# OpenBook_v38.net
KiCad netlist of a schematic drawn in EAGLE
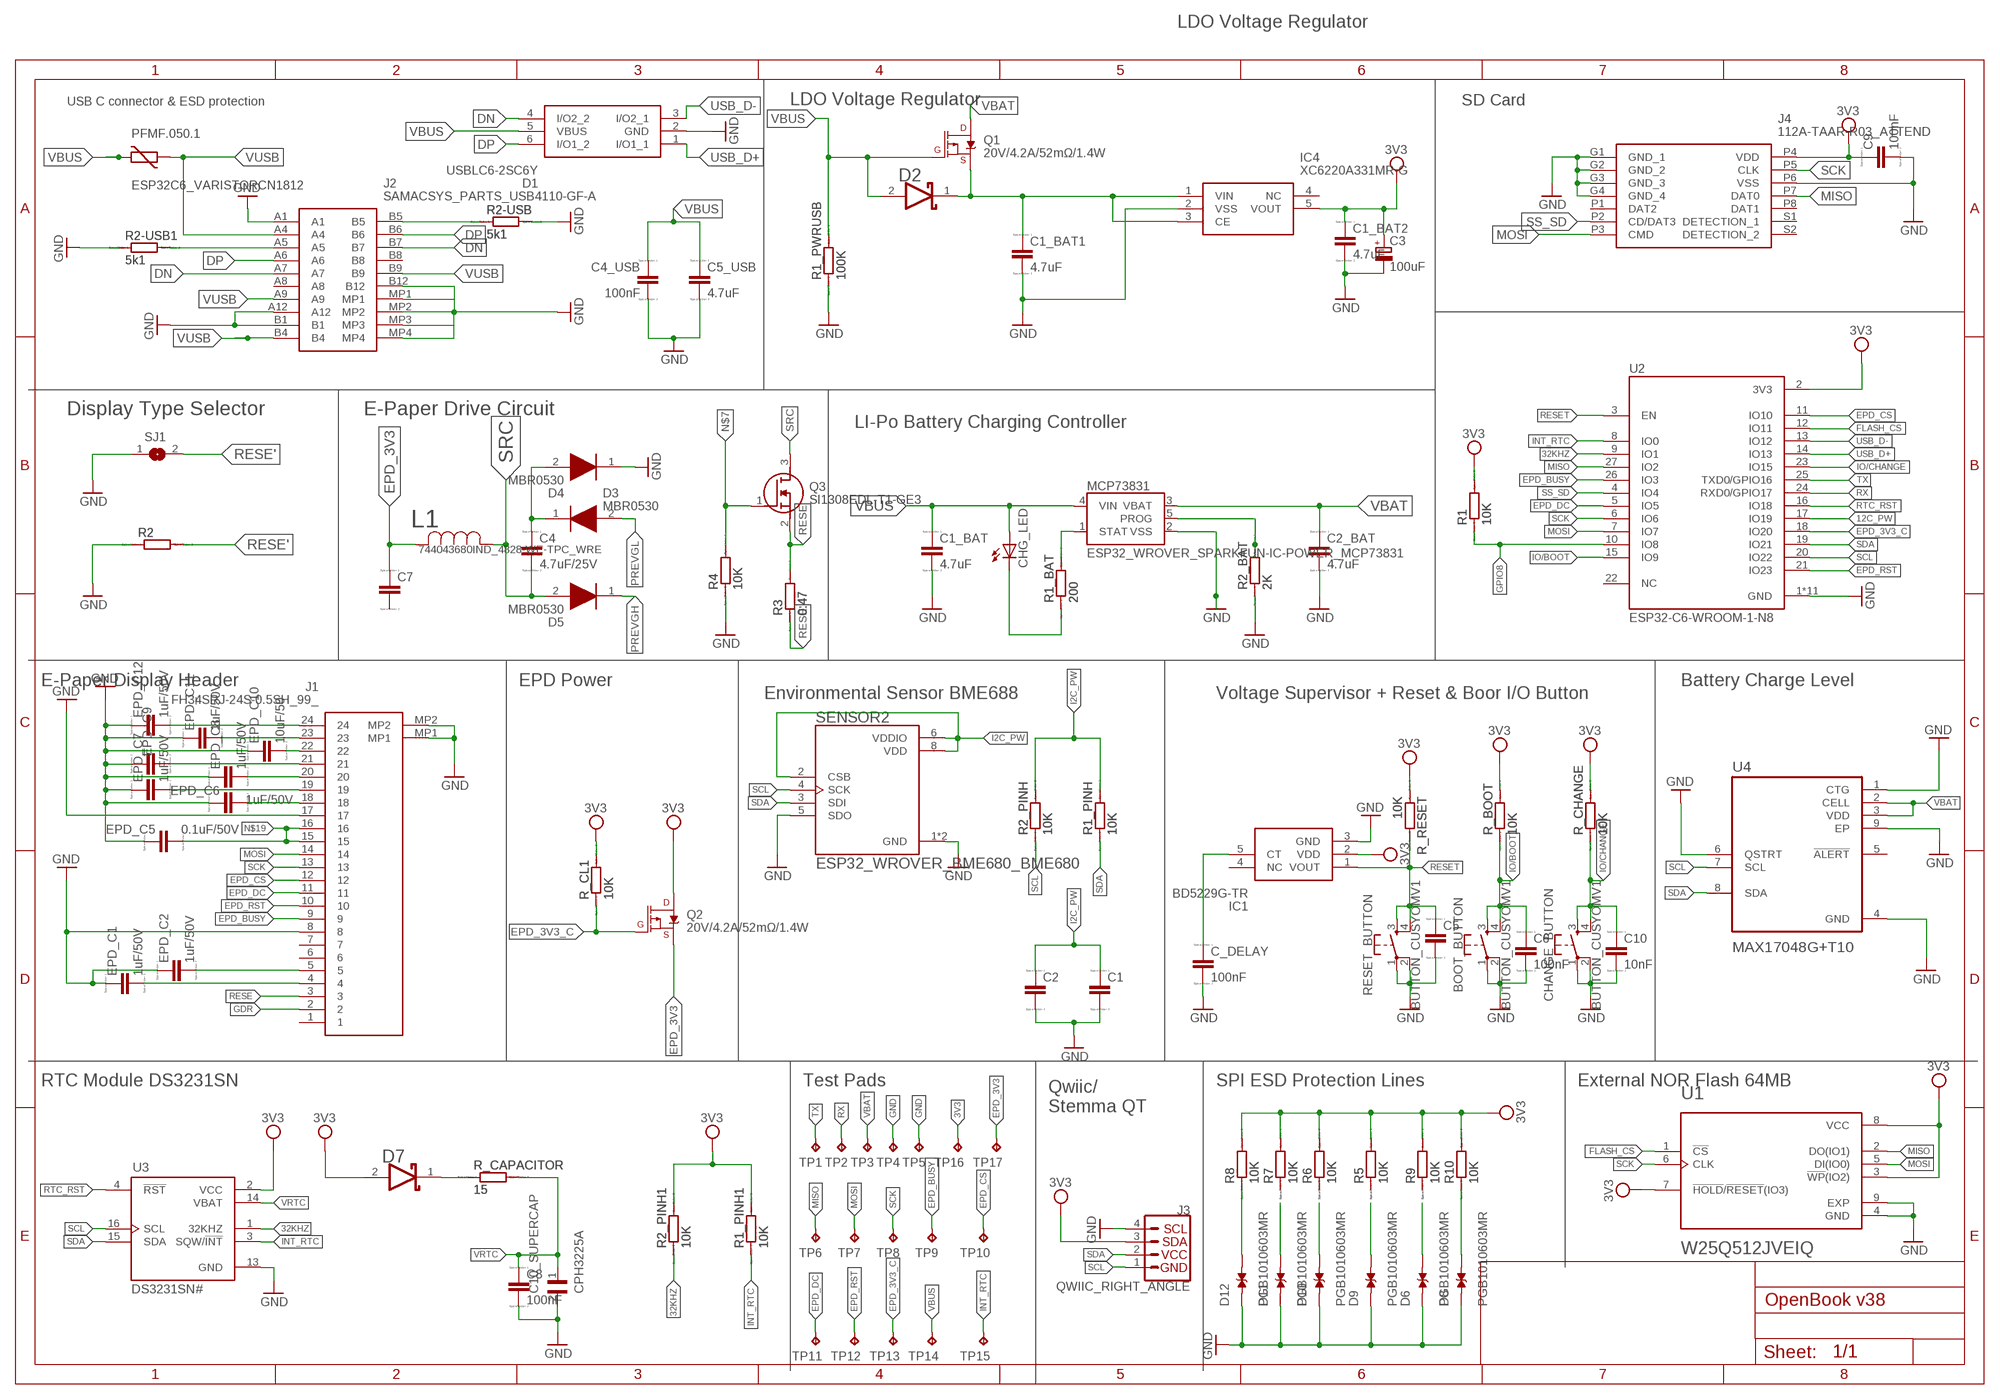
[diagram p0: schematic, sheet 1]

(export (version "E")
  (design (tool "Eeschema 10.0.6"))
  (components
    (comp (ref "BOOT_BUTTON")
      (value "BUTTON_CUSYOMV1")
      (footprint "eagle-import:MYBUTTON")
      (libsource (lib "eagle-import") (part "BUTTON_CUSYOMV1"))
    )
    (comp (ref "C1")
      (value "EAGLE-LTSPICE_CC0402")
      (footprint "eagle-import:EAGLE-LTSPICE_C0402")
      (libsource (lib "eagle-import") (part "EAGLE-LTSPICE_CC0402"))
    )
    (comp (ref "C1_BAT")
      (value "4.7uF")
      (footprint "eagle-import:EAGLE-LTSPICE_C0402")
      (libsource (lib "eagle-import") (part "EAGLE-LTSPICE_CC0402"))
    )
    (comp (ref "C1_BAT1")
      (value "4.7uF")
      (footprint "eagle-import:EAGLE-LTSPICE_C0402")
      (libsource (lib "eagle-import") (part "EAGLE-LTSPICE_CC0402"))
    )
    (comp (ref "C1_BAT2")
      (value "4.7uF")
      (footprint "eagle-import:EAGLE-LTSPICE_C0402")
      (libsource (lib "eagle-import") (part "EAGLE-LTSPICE_CC0402"))
    )
    (comp (ref "C2")
      (value "EAGLE-LTSPICE_CC0402")
      (footprint "eagle-import:EAGLE-LTSPICE_C0402")
      (libsource (lib "eagle-import") (part "EAGLE-LTSPICE_CC0402"))
    )
    (comp (ref "C2_BAT")
      (value "4.7uF")
      (footprint "eagle-import:EAGLE-LTSPICE_C0402")
      (libsource (lib "eagle-import") (part "EAGLE-LTSPICE_CC0402"))
    )
    (comp (ref "C3")
      (value "100uF")
      (footprint "eagle-import:RCL_CT3528")
      (libsource (lib "eagle-import") (part "RCL_CPOL-EUCT3528"))
    )
    (comp (ref "C4")
      (value "4.7uF/25V")
      (footprint "eagle-import:EAGLE-LTSPICE_C0402")
      (libsource (lib "eagle-import") (part "EAGLE-LTSPICE_CC0402"))
    )
    (comp (ref "C4_USB")
      (value "100nF")
      (footprint "eagle-import:EAGLE-LTSPICE_C0402")
      (libsource (lib "eagle-import") (part "EAGLE-LTSPICE_CC0402"))
    )
    (comp (ref "C5")
      (value "EAGLE-LTSPICE_CC0402")
      (footprint "eagle-import:EAGLE-LTSPICE_C0402")
      (libsource (lib "eagle-import") (part "EAGLE-LTSPICE_CC0402"))
    )
    (comp (ref "C5_USB")
      (value "4.7uF")
      (footprint "eagle-import:EAGLE-LTSPICE_C0402")
      (libsource (lib "eagle-import") (part "EAGLE-LTSPICE_CC0402"))
    )
    (comp (ref "C6")
      (value "100nF")
      (footprint "eagle-import:EAGLE-LTSPICE_C0402")
      (libsource (lib "eagle-import") (part "EAGLE-LTSPICE_CC0402"))
    )
    (comp (ref "C7")
      (value "EAGLE-LTSPICE_CC0402")
      (footprint "eagle-import:EAGLE-LTSPICE_C0402")
      (libsource (lib "eagle-import") (part "EAGLE-LTSPICE_CC0402"))
    )
    (comp (ref "C8")
      (value "100nF")
      (footprint "eagle-import:EAGLE-LTSPICE_C0402")
      (libsource (lib "eagle-import") (part "EAGLE-LTSPICE_CC0402"))
    )
    (comp (ref "C9")
      (value "100nF")
      (footprint "eagle-import:EAGLE-LTSPICE_C0402")
      (libsource (lib "eagle-import") (part "EAGLE-LTSPICE_CC0402"))
    )
    (comp (ref "C10")
      (value "10nF")
      (footprint "eagle-import:EAGLE-LTSPICE_C0402")
      (libsource (lib "eagle-import") (part "EAGLE-LTSPICE_CC0402"))
    )
    (comp (ref "C10_SUPERCAP")
      (value "CPH3225A")
      (footprint "eagle-import:CAPCP3225X100N")
      (fields (field (name "MF") "Seiko Instruments"))
      (libsource (lib "eagle-import") (part "CPH3225A"))
    )
    (comp (ref "CHANGE_BUTTON")
      (value "BUTTON_CUSYOMV1")
      (footprint "eagle-import:MYBUTTON")
      (libsource (lib "eagle-import") (part "BUTTON_CUSYOMV1"))
    )
    (comp (ref "CHG_LED")
      (value "ADAFRUIT_LEDCHIP-LED0603")
      (footprint "eagle-import:ADAFRUIT_CHIP-LED0603")
      (libsource (lib "eagle-import") (part "ADAFRUIT_LEDCHIP-LED0603"))
    )
    (comp (ref "C_DELAY")
      (value "100nF")
      (footprint "eagle-import:EAGLE-LTSPICE_C0402")
      (libsource (lib "eagle-import") (part "EAGLE-LTSPICE_CC0402"))
    )
    (comp (ref "D1")
      (value "USBLC6-2SC6Y")
      (footprint "eagle-import:SOT95P280X145-6N")
      (fields (field (name "MF") "STMicroelectronics"))
      (libsource (lib "eagle-import") (part "USBLC6-2SC6Y"))
    )
    (comp (ref "D2")
      (value "ESP32_WROVER_AVX---SD0805S020S1R0_AVX_SD0805S020S1R0_0_0AVX_SD0805S020S1R0_0_0")
      (footprint "eagle-import:ESP32_WROVER_AVX---SD0805S020S1R0_AVX_SD0805S020S1R0_0")
      (fields
        (field (name "DIGIKEY_PART_NUMBER") "478-7800-1-ND")
        (field (name "MF") "AVX")
        (field (name "MOUSER_PART_NUMBER") "581-SD0805S020S1R0")
      )
      (libsource (lib "eagle-import") (part "ESP32_WROVER_AVX---SD0805S020S1R0_AVX_SD0805S020S1R0_0_0AVX_SD0805S020S1R0_0_0"))
    )
    (comp (ref "D3")
      (value "MBR0530")
      (footprint "eagle-import:SOD3716X135N")
      (fields (field (name "MF") "ON Semiconductor"))
      (libsource (lib "eagle-import") (part "MBR0530"))
    )
    (comp (ref "D4")
      (value "MBR0530")
      (footprint "eagle-import:SOD3716X135N")
      (fields (field (name "MF") "ON Semiconductor"))
      (libsource (lib "eagle-import") (part "MBR0530"))
    )
    (comp (ref "D5")
      (value "MBR0530")
      (footprint "eagle-import:SOD3716X135N")
      (fields (field (name "MF") "ON Semiconductor"))
      (libsource (lib "eagle-import") (part "MBR0530"))
    )
    (comp (ref "D6")
      (value "PGB1010603MR")
      (footprint "eagle-import:DIOC1608X36N")
      (fields (field (name "MF") "Littelfuse Inc."))
      (libsource (lib "eagle-import") (part "PGB1010603MR"))
    )
    (comp (ref "D7")
      (value "ESP32_WROVER_AVX---SD0805S020S1R0_AVX_SD0805S020S1R0_0_0AVX_SD0805S020S1R0_0_0")
      (footprint "eagle-import:ESP32_WROVER_AVX---SD0805S020S1R0_AVX_SD0805S020S1R0_0")
      (fields
        (field (name "DIGIKEY_PART_NUMBER") "478-7800-1-ND")
        (field (name "MF") "AVX")
        (field (name "MOUSER_PART_NUMBER") "581-SD0805S020S1R0")
      )
      (libsource (lib "eagle-import") (part "ESP32_WROVER_AVX---SD0805S020S1R0_AVX_SD0805S020S1R0_0_0AVX_SD0805S020S1R0_0_0"))
    )
    (comp (ref "D8")
      (value "PGB1010603MR")
      (footprint "eagle-import:DIOC1608X36N")
      (fields (field (name "MF") "Littelfuse Inc."))
      (libsource (lib "eagle-import") (part "PGB1010603MR"))
    )
    (comp (ref "D9")
      (value "PGB1010603MR")
      (footprint "eagle-import:DIOC1608X36N")
      (fields (field (name "MF") "Littelfuse Inc."))
      (libsource (lib "eagle-import") (part "PGB1010603MR"))
    )
    (comp (ref "D10")
      (value "PGB1010603MR")
      (footprint "eagle-import:DIOC1608X36N")
      (fields (field (name "MF") "Littelfuse Inc."))
      (libsource (lib "eagle-import") (part "PGB1010603MR"))
    )
    (comp (ref "D11")
      (value "PGB1010603MR")
      (footprint "eagle-import:DIOC1608X36N")
      (fields (field (name "MF") "Littelfuse Inc."))
      (libsource (lib "eagle-import") (part "PGB1010603MR"))
    )
    (comp (ref "D12")
      (value "PGB1010603MR")
      (footprint "eagle-import:DIOC1608X36N")
      (fields (field (name "MF") "Littelfuse Inc."))
      (libsource (lib "eagle-import") (part "PGB1010603MR"))
    )
    (comp (ref "EPD_C1")
      (value "1uF/50V")
      (footprint "eagle-import:EAGLE-LTSPICE_C0402")
      (libsource (lib "eagle-import") (part "EAGLE-LTSPICE_CC0402"))
    )
    (comp (ref "EPD_C2")
      (value "1uF/50V")
      (footprint "eagle-import:EAGLE-LTSPICE_C0402")
      (libsource (lib "eagle-import") (part "EAGLE-LTSPICE_CC0402"))
    )
    (comp (ref "EPD_C5")
      (value "0.1uF/50V")
      (footprint "eagle-import:EAGLE-LTSPICE_C0402")
      (libsource (lib "eagle-import") (part "EAGLE-LTSPICE_CC0402"))
    )
    (comp (ref "EPD_C6")
      (value "1uF/50V")
      (footprint "eagle-import:EAGLE-LTSPICE_C0402")
      (libsource (lib "eagle-import") (part "EAGLE-LTSPICE_CC0402"))
    )
    (comp (ref "EPD_C7")
      (value "1uF/50V")
      (footprint "eagle-import:EAGLE-LTSPICE_C0402")
      (libsource (lib "eagle-import") (part "EAGLE-LTSPICE_CC0402"))
    )
    (comp (ref "EPD_C8")
      (value "1uF/50V")
      (footprint "eagle-import:EAGLE-LTSPICE_C0402")
      (libsource (lib "eagle-import") (part "EAGLE-LTSPICE_CC0402"))
    )
    (comp (ref "EPD_C9")
      (value "EAGLE-LTSPICE_CC0402")
      (footprint "eagle-import:EAGLE-LTSPICE_C0402")
      (libsource (lib "eagle-import") (part "EAGLE-LTSPICE_CC0402"))
    )
    (comp (ref "EPD_C10")
      (value "10uF/50")
      (footprint "eagle-import:EAGLE-LTSPICE_C0402")
      (libsource (lib "eagle-import") (part "EAGLE-LTSPICE_CC0402"))
    )
    (comp (ref "EPD_C11")
      (value "1uF/50V")
      (footprint "eagle-import:EAGLE-LTSPICE_C0402")
      (libsource (lib "eagle-import") (part "EAGLE-LTSPICE_CC0402"))
    )
    (comp (ref "EPD_C12")
      (value "1uF/50V")
      (footprint "eagle-import:EAGLE-LTSPICE_C0402")
      (libsource (lib "eagle-import") (part "EAGLE-LTSPICE_CC0402"))
    )
    (comp (ref "IC1")
      (value "BD5229G-TR")
      (footprint "eagle-import:SOT95P280X125-5N")
      (fields (field (name "MOUSER_PART_NUMBER") "755-BD5229G-TR"))
      (libsource (lib "eagle-import") (part "BD5229G-TR"))
    )
    (comp (ref "IC4")
      (value "XC6220A331MR-G")
      (footprint "eagle-import:SOT95P280X120-5N")
      (fields (field (name "MOUSER_PART_NUMBER") "865-XC6220A331MR-G"))
      (libsource (lib "eagle-import") (part "XC6220A331MR-G"))
    )
    (comp (ref "J1")
      (value "FH34SRJ-24S-0.5SH_99_")
      (footprint "eagle-import:FH34SRJ24S05SH99")
      (fields
        (field (name "MANUFACTURER_PART_NUMBER") "FH34SRJ-24S-0.5SH(99)")
        (field (name "MOUSER_PART_NUMBER") "798-FH34SRJ24S05SH99")
      )
      (libsource (lib "eagle-import") (part "FH34SRJ-24S-0.5SH_99_"))
    )
    (comp (ref "J2")
      (value "SAMACSYS_PARTS_USB4110-GF-A")
      (footprint "eagle-import:SAMACSYS_PARTS_USB4110GFA")
      (fields
        (field (name "MANUFACTURER_PART_NUMBER") "USB4110-GF-A")
        (field (name "MOUSER_PART_NUMBER") "640-USB4110-GF-A")
      )
      (libsource (lib "eagle-import") (part "SAMACSYS_PARTS_USB4110-GF-A"))
    )
    (comp (ref "J3")
      (value "QWIIC_RIGHT_ANGLE")
      (footprint "eagle-import:JST04_1MM_RA")
      (libsource (lib "eagle-import") (part "QWIIC_CONNECTORJS-1MM"))
    )
    (comp (ref "J4")
      (value "112A-TAAR-R03_ATTEND")
      (footprint "eagle-import:112ATAARR03ATTEND")
      (fields (field (name "MANUFACTURER_PART_NUMBER") "112A-TAAR-R03 ATTEND"))
      (libsource (lib "eagle-import") (part "112A-TAAR-R03_ATTEND"))
    )
    (comp (ref "L1")
      (value "744043680IND_4828-WE-TPC_WRE")
      (footprint "eagle-import:IND_4828-WE-TPC_WRE")
      (fields
        (field (name "MANUFACTURER_PART_NUMBER") "744043680")
        (field (name "COPYRIGHT") "Copyright (C) 2024 Ultra Librarian. All rights reserved.")
      )
      (libsource (lib "eagle-import") (part "744043680IND_4828-WE-TPC_WRE"))
    )
    (comp (ref "MCP73831")
      (value "ESP32_WROVER_SPARKFUN-IC-POWER_MCP73831")
      (footprint "eagle-import:ESP32_WROVER_SPARKFUN-IC-POWER_SOT23-5")
      (libsource (lib "eagle-import") (part "ESP32_WROVER_SPARKFUN-IC-POWER_MCP73831"))
    )
    (comp (ref "PFMF.050.1")
      (value "ESP32C6_VARISTORCN1812")
      (footprint "eagle-import:ESP32C6_VARISTOR_CT_CN1812")
      (libsource (lib "eagle-import") (part "ESP32C6_VARISTORCN1812"))
    )
    (comp (ref "Q1")
      (value "20V/4.2A/52mΩ/1.4W")
      (footprint "eagle-import:ESP32_WROVER_SPARKFUN-DISCRETESEMI_SOT23-3")
      (libsource (lib "eagle-import") (part "ESP32_WROVER_SPARKFUN-DISCRETESEMI_MOSFET_PCH-DMG2305UX-7"))
    )
    (comp (ref "Q2")
      (value "20V/4.2A/52mΩ/1.4W")
      (footprint "eagle-import:ESP32_WROVER_SPARKFUN-DISCRETESEMI_SOT23-3")
      (libsource (lib "eagle-import") (part "ESP32_WROVER_SPARKFUN-DISCRETESEMI_MOSFET_PCH-DMG2305UX-7"))
    )
    (comp (ref "Q3")
      (value "SI1308EDL-T1-GE3")
      (footprint "eagle-import:SOT65P210X110-3N")
      (fields (field (name "MF") "Vishay Siliconix"))
      (libsource (lib "eagle-import") (part "SI1308EDL-T1-GE3"))
    )
    (comp (ref "R1")
      (value "10K")
      (footprint "eagle-import:ESP32_WROVER_EAGLE-LTSPICE_R0402")
      (libsource (lib "eagle-import") (part "ESP32_WROVER_EAGLE-LTSPICE_RR0402"))
    )
    (comp (ref "R1_BAT")
      (value "200")
      (footprint "eagle-import:ESP32_WROVER_EAGLE-LTSPICE_R0402")
      (libsource (lib "eagle-import") (part "ESP32_WROVER_EAGLE-LTSPICE_RR0402"))
    )
    (comp (ref "R1_PINH")
      (value "10K")
      (footprint "eagle-import:ESP32_WROVER_EAGLE-LTSPICE_R0402")
      (libsource (lib "eagle-import") (part "ESP32_WROVER_EAGLE-LTSPICE_RR0402"))
    )
    (comp (ref "R1_PINH1")
      (value "10K")
      (footprint "eagle-import:ESP32_WROVER_EAGLE-LTSPICE_R0402")
      (libsource (lib "eagle-import") (part "ESP32_WROVER_EAGLE-LTSPICE_RR0402"))
    )
    (comp (ref "R1_PWRUSB")
      (value "100K")
      (footprint "eagle-import:ESP32_WROVER_EAGLE-LTSPICE_R0402")
      (libsource (lib "eagle-import") (part "ESP32_WROVER_EAGLE-LTSPICE_RR0402"))
    )
    (comp (ref "R2")
      (value "ESP32_WROVER_EAGLE-LTSPICE_RR0402")
      (footprint "eagle-import:ESP32_WROVER_EAGLE-LTSPICE_R0402")
      (libsource (lib "eagle-import") (part "ESP32_WROVER_EAGLE-LTSPICE_RR0402"))
    )
    (comp (ref "R2-USB")
      (value "5k1")
      (footprint "eagle-import:ESP32_WROVER_EAGLE-LTSPICE_R0402")
      (libsource (lib "eagle-import") (part "ESP32_WROVER_EAGLE-LTSPICE_RR0402"))
    )
    (comp (ref "R2-USB1")
      (value "5k1")
      (footprint "eagle-import:ESP32_WROVER_EAGLE-LTSPICE_R0402")
      (libsource (lib "eagle-import") (part "ESP32_WROVER_EAGLE-LTSPICE_RR0402"))
    )
    (comp (ref "R2_BAT")
      (value "2K")
      (footprint "eagle-import:ESP32_WROVER_EAGLE-LTSPICE_R0402")
      (libsource (lib "eagle-import") (part "ESP32_WROVER_EAGLE-LTSPICE_RR0402"))
    )
    (comp (ref "R2_PINH")
      (value "10K")
      (footprint "eagle-import:ESP32_WROVER_EAGLE-LTSPICE_R0402")
      (libsource (lib "eagle-import") (part "ESP32_WROVER_EAGLE-LTSPICE_RR0402"))
    )
    (comp (ref "R2_PINH1")
      (value "10K")
      (footprint "eagle-import:ESP32_WROVER_EAGLE-LTSPICE_R0402")
      (libsource (lib "eagle-import") (part "ESP32_WROVER_EAGLE-LTSPICE_RR0402"))
    )
    (comp (ref "R3")
      (value "0.47")
      (footprint "eagle-import:ESP32_WROVER_EAGLE-LTSPICE_R0402")
      (libsource (lib "eagle-import") (part "ESP32_WROVER_EAGLE-LTSPICE_RR0402"))
    )
    (comp (ref "R4")
      (value "10K")
      (footprint "eagle-import:ESP32_WROVER_EAGLE-LTSPICE_R0402")
      (libsource (lib "eagle-import") (part "ESP32_WROVER_EAGLE-LTSPICE_RR0402"))
    )
    (comp (ref "R5")
      (value "10K")
      (footprint "eagle-import:ESP32_WROVER_EAGLE-LTSPICE_R0402")
      (libsource (lib "eagle-import") (part "ESP32_WROVER_EAGLE-LTSPICE_RR0402"))
    )
    (comp (ref "R6")
      (value "10K")
      (footprint "eagle-import:ESP32_WROVER_EAGLE-LTSPICE_R0402")
      (libsource (lib "eagle-import") (part "ESP32_WROVER_EAGLE-LTSPICE_RR0402"))
    )
    (comp (ref "R7")
      (value "10K")
      (footprint "eagle-import:ESP32_WROVER_EAGLE-LTSPICE_R0402")
      (libsource (lib "eagle-import") (part "ESP32_WROVER_EAGLE-LTSPICE_RR0402"))
    )
    (comp (ref "R8")
      (value "10K")
      (footprint "eagle-import:ESP32_WROVER_EAGLE-LTSPICE_R0402")
      (libsource (lib "eagle-import") (part "ESP32_WROVER_EAGLE-LTSPICE_RR0402"))
    )
    (comp (ref "R9")
      (value "10K")
      (footprint "eagle-import:ESP32_WROVER_EAGLE-LTSPICE_R0402")
      (libsource (lib "eagle-import") (part "ESP32_WROVER_EAGLE-LTSPICE_RR0402"))
    )
    (comp (ref "R10")
      (value "10K")
      (footprint "eagle-import:ESP32_WROVER_EAGLE-LTSPICE_R0402")
      (libsource (lib "eagle-import") (part "ESP32_WROVER_EAGLE-LTSPICE_RR0402"))
    )
    (comp (ref "RESET_BUTTON")
      (value "BUTTON_CUSYOMV1")
      (footprint "eagle-import:MYBUTTON")
      (libsource (lib "eagle-import") (part "BUTTON_CUSYOMV1"))
    )
    (comp (ref "R_BOOT")
      (value "10K")
      (footprint "eagle-import:ESP32_WROVER_EAGLE-LTSPICE_R0402")
      (libsource (lib "eagle-import") (part "ESP32_WROVER_EAGLE-LTSPICE_RR0402"))
    )
    (comp (ref "R_CAPACITOR")
      (value "15")
      (footprint "eagle-import:ESP32_WROVER_EAGLE-LTSPICE_R0402")
      (libsource (lib "eagle-import") (part "ESP32_WROVER_EAGLE-LTSPICE_RR0402"))
    )
    (comp (ref "R_CHANGE")
      (value "10K")
      (footprint "eagle-import:ESP32_WROVER_EAGLE-LTSPICE_R0402")
      (libsource (lib "eagle-import") (part "ESP32_WROVER_EAGLE-LTSPICE_RR0402"))
    )
    (comp (ref "R_CL1")
      (value "10K")
      (footprint "eagle-import:ESP32_WROVER_EAGLE-LTSPICE_R0402")
      (libsource (lib "eagle-import") (part "ESP32_WROVER_EAGLE-LTSPICE_RR0402"))
    )
    (comp (ref "R_RESET")
      (value "10K")
      (footprint "eagle-import:ESP32_WROVER_EAGLE-LTSPICE_R0402")
      (libsource (lib "eagle-import") (part "ESP32_WROVER_EAGLE-LTSPICE_RR0402"))
    )
    (comp (ref "SENSOR2")
      (value "ESP32_WROVER_BME680_BME680")
      (footprint "eagle-import:ESP32_WROVER_BME680_PSON80P300X300X100-8N")
      (fields (field (name "MF") "Bosch Sensortec") (field (name "MP") "BME680"))
      (libsource (lib "eagle-import") (part "ESP32_WROVER_BME680_BME680"))
    )
    (comp (ref "SJ1") (value "SJ") (footprint "eagle-import:SJ") (libsource (lib "eagle-import") (part "SJ")))
    (comp (ref "TP1")
      (value "TPTP20R")
      (footprint "eagle-import:TP20R")
      (libsource (lib "eagle-import") (part "TPTP20R"))
    )
    (comp (ref "TP2")
      (value "TPTP20R")
      (footprint "eagle-import:TP20R")
      (libsource (lib "eagle-import") (part "TPTP20R"))
    )
    (comp (ref "TP3")
      (value "TPTP20R")
      (footprint "eagle-import:TP20R")
      (libsource (lib "eagle-import") (part "TPTP20R"))
    )
    (comp (ref "TP4")
      (value "TPTP20R")
      (footprint "eagle-import:TP20R")
      (libsource (lib "eagle-import") (part "TPTP20R"))
    )
    (comp (ref "TP5")
      (value "TPTP20R")
      (footprint "eagle-import:TP20R")
      (libsource (lib "eagle-import") (part "TPTP20R"))
    )
    (comp (ref "TP6")
      (value "TPTP20R")
      (footprint "eagle-import:TP20R")
      (libsource (lib "eagle-import") (part "TPTP20R"))
    )
    (comp (ref "TP7")
      (value "TPTP20R")
      (footprint "eagle-import:TP20R")
      (libsource (lib "eagle-import") (part "TPTP20R"))
    )
    (comp (ref "TP8")
      (value "TPTP20R")
      (footprint "eagle-import:TP20R")
      (libsource (lib "eagle-import") (part "TPTP20R"))
    )
    (comp (ref "TP9")
      (value "TPTP20R")
      (footprint "eagle-import:TP20R")
      (libsource (lib "eagle-import") (part "TPTP20R"))
    )
    (comp (ref "TP10")
      (value "TPTP20R")
      (footprint "eagle-import:TP20R")
      (libsource (lib "eagle-import") (part "TPTP20R"))
    )
    (comp (ref "TP11")
      (value "TPTP20R")
      (footprint "eagle-import:TP20R")
      (libsource (lib "eagle-import") (part "TPTP20R"))
    )
    (comp (ref "TP12")
      (value "TPTP20R")
      (footprint "eagle-import:TP20R")
      (libsource (lib "eagle-import") (part "TPTP20R"))
    )
    (comp (ref "TP13")
      (value "TPTP20R")
      (footprint "eagle-import:TP20R")
      (libsource (lib "eagle-import") (part "TPTP20R"))
    )
    (comp (ref "TP14")
      (value "TPTP20R")
      (footprint "eagle-import:TP20R")
      (libsource (lib "eagle-import") (part "TPTP20R"))
    )
    (comp (ref "TP15")
      (value "TPTP20R")
      (footprint "eagle-import:TP20R")
      (libsource (lib "eagle-import") (part "TPTP20R"))
    )
    (comp (ref "TP16")
      (value "TPTP20R")
      (footprint "eagle-import:TP20R")
      (libsource (lib "eagle-import") (part "TPTP20R"))
    )
    (comp (ref "TP17")
      (value "TPTP20R")
      (footprint "eagle-import:TP20R")
      (libsource (lib "eagle-import") (part "TPTP20R"))
    )
    (comp (ref "U1")
      (value "W25Q512JVEIQ")
      (footprint "eagle-import:SON127P600X800X80-9N")
      (fields (field (name "MF") "Winbond Electronics"))
      (libsource (lib "eagle-import") (part "W25Q512JVEIQ"))
    )
    (comp (ref "U2")
      (value "ESP32-C6-WROOM-1-N8")
      (footprint "eagle-import:XCVR_ESP32-C6-WROOM-1-N8")
      (fields (field (name "MF") "Espressif Systems"))
      (libsource (lib "eagle-import") (part "ESP32-C6-WROOM-1-N8"))
    )
    (comp (ref "U3")
      (value "DS3231SN#")
      (footprint "eagle-import:SOIC127P1032X265-16N")
      (fields (field (name "MF") "Analog Devices"))
      (libsource (lib "eagle-import") (part "DS3231SN#"))
    )
    (comp (ref "U4")
      (value "MAX17048G+T10")
      (footprint "eagle-import:SON50P200X200X80-9N")
      (fields (field (name "MF") "Analog Devices"))
      (libsource (lib "eagle-import") (part "MAX17048G+T10"))
    )
  )
  (nets
    (net (code "1") (name "3V3") (class "Default")
      (node (ref "C1_BAT2") (pin "1") (pinfunction "1_1") (pintype "passive"))
      (node (ref "C3") (pin "+") (pinfunction "+_+") (pintype "passive"))
      (node (ref "C9") (pin "1") (pinfunction "1_1") (pintype "passive"))
      (node (ref "D7") (pin "2") (pinfunction "ANODE_2") (pintype "bidirectional"))
      (node (ref "IC1") (pin "2") (pinfunction "VDD_2") (pintype "bidirectional"))
      (node (ref "IC4") (pin "5") (pinfunction "VOUT_5") (pintype "bidirectional"))
      (node (ref "J3") (pin "3") (pinfunction "3_3") (pintype "passive"))
      (node (ref "J4") (pin "P4") (pinfunction "VDD_P4") (pintype "bidirectional"))
      (node (ref "Q2") (pin "3") (pinfunction "D_3") (pintype "bidirectional"))
      (node (ref "R1") (pin "2") (pinfunction "2_2") (pintype "passive"))
      (node (ref "R10") (pin "2") (pinfunction "2_2") (pintype "passive"))
      (node (ref "R1_PINH1") (pin "2") (pinfunction "2_2") (pintype "passive"))
      (node (ref "R2_PINH1") (pin "2") (pinfunction "2_2") (pintype "passive"))
      (node (ref "R5") (pin "2") (pinfunction "2_2") (pintype "passive"))
      (node (ref "R6") (pin "2") (pinfunction "2_2") (pintype "passive"))
      (node (ref "R7") (pin "2") (pinfunction "2_2") (pintype "passive"))
      (node (ref "R8") (pin "2") (pinfunction "2_2") (pintype "passive"))
      (node (ref "R9") (pin "2") (pinfunction "2_2") (pintype "passive"))
      (node (ref "R_BOOT") (pin "2") (pinfunction "2_2") (pintype "passive"))
      (node (ref "R_CHANGE") (pin "2") (pinfunction "2_2") (pintype "passive"))
      (node (ref "R_CL1") (pin "2") (pinfunction "2_2") (pintype "passive"))
      (node (ref "R_RESET") (pin "1") (pinfunction "1_1") (pintype "passive"))
      (node (ref "TP16") (pin "TP") (pinfunction "TP_TP") (pintype "input"))
      (node (ref "U1") (pin "3") (pinfunction "~{WP}(IO2)_3") (pintype "bidirectional"))
      (node (ref "U1") (pin "7") (pinfunction "~{HOLD}/~{RESET}(IO3)_7") (pintype "bidirectional"))
      (node (ref "U1") (pin "8") (pinfunction "VCC_8") (pintype "power_in"))
      (node (ref "U2") (pin "2") (pinfunction "3V3_2") (pintype "power_in"))
      (node (ref "U3") (pin "2") (pinfunction "VCC_2") (pintype "power_in"))
    )
    (net (code "2") (name "12C_PW") (class "Default")
      (node (ref "U2") (pin "17") (pinfunction "IO19_17") (pintype "bidirectional"))
    )
    (net (code "3") (name "32KHZ") (class "Default")
      (node (ref "R2_PINH1") (pin "1") (pinfunction "1_1") (pintype "passive"))
      (node (ref "U2") (pin "9") (pinfunction "IO1_9") (pintype "bidirectional"))
      (node (ref "U3") (pin "1") (pinfunction "32KHZ_1") (pintype "output"))
    )
    (net (code "4") (name "DN") (class "Default")
      (node (ref "D1") (pin "4") (pinfunction "I/O2_2_4") (pintype "bidirectional"))
      (node (ref "J2") (pin "A7") (pinfunction "A7_A7") (pintype "bidirectional"))
      (node (ref "J2") (pin "B7") (pinfunction "B7_B7") (pintype "bidirectional"))
    )
    (net (code "5") (name "DP") (class "Default")
      (node (ref "D1") (pin "6") (pinfunction "I/O1_2_6") (pintype "bidirectional"))
      (node (ref "J2") (pin "A6") (pinfunction "A6_A6") (pintype "bidirectional"))
      (node (ref "J2") (pin "B6") (pinfunction "B6_B6") (pintype "bidirectional"))
    )
    (net (code "6") (name "EPD_3V3") (class "Default")
      (node (ref "C7") (pin "1") (pinfunction "1_1") (pintype "passive"))
      (node (ref "L1") (pin "2") (pinfunction "2_2") (pintype "passive"))
      (node (ref "Q2") (pin "2") (pinfunction "S_2") (pintype "bidirectional"))
      (node (ref "TP17") (pin "TP") (pinfunction "TP_TP") (pintype "input"))
    )
    (net (code "7") (name "EPD_3V3_C") (class "Default")
      (node (ref "Q2") (pin "1") (pinfunction "G_1") (pintype "bidirectional"))
      (node (ref "R_CL1") (pin "1") (pinfunction "1_1") (pintype "passive"))
      (node (ref "TP13") (pin "TP") (pinfunction "TP_TP") (pintype "input"))
      (node (ref "U2") (pin "18") (pinfunction "IO20_18") (pintype "bidirectional"))
    )
    (net (code "8") (name "EPD_BUSY") (class "Default")
      (node (ref "J1") (pin "9") (pinfunction "9_9") (pintype "bidirectional"))
      (node (ref "TP9") (pin "TP") (pinfunction "TP_TP") (pintype "input"))
      (node (ref "U2") (pin "26") (pinfunction "IO3_26") (pintype "bidirectional"))
    )
    (net (code "9") (name "EPD_CS") (class "Default")
      (node (ref "J1") (pin "12") (pinfunction "12_12") (pintype "bidirectional"))
      (node (ref "TP10") (pin "TP") (pinfunction "TP_TP") (pintype "input"))
      (node (ref "U2") (pin "11") (pinfunction "IO10_11") (pintype "bidirectional"))
    )
    (net (code "10") (name "EPD_DC") (class "Default")
      (node (ref "J1") (pin "11") (pinfunction "11_11") (pintype "bidirectional"))
      (node (ref "TP11") (pin "TP") (pinfunction "TP_TP") (pintype "input"))
      (node (ref "U2") (pin "5") (pinfunction "IO5_5") (pintype "bidirectional"))
    )
    (net (code "11") (name "EPD_RST") (class "Default")
      (node (ref "J1") (pin "10") (pinfunction "10_10") (pintype "bidirectional"))
      (node (ref "TP12") (pin "TP") (pinfunction "TP_TP") (pintype "input"))
      (node (ref "U2") (pin "21") (pinfunction "IO23_21") (pintype "bidirectional"))
    )
    (net (code "12") (name "FLASH_CS") (class "Default")
      (node (ref "U1") (pin "1") (pinfunction "~{CS}_1") (pintype "input"))
      (node (ref "U2") (pin "12") (pinfunction "IO11_12") (pintype "bidirectional"))
    )
    (net (code "13") (name "GDR") (class "Default")
      (node (ref "J1") (pin "2") (pinfunction "2_2") (pintype "bidirectional"))
    )
    (net (code "14") (name "GND") (class "Default")
      (node (ref "BOOT_BUTTON") (pin "1") (pinfunction "1_1") (pintype "passive"))
      (node (ref "BOOT_BUTTON") (pin "2") (pinfunction "2_2") (pintype "passive"))
      (node (ref "C1") (pin "2") (pinfunction "2_2") (pintype "passive"))
      (node (ref "C10") (pin "2") (pinfunction "2_2") (pintype "passive"))
      (node (ref "C10_SUPERCAP") (pin "2") (pinfunction "2_2") (pintype "passive"))
      (node (ref "C1_BAT") (pin "2") (pinfunction "2_2") (pintype "passive"))
      (node (ref "C1_BAT1") (pin "2") (pinfunction "2_2") (pintype "passive"))
      (node (ref "C1_BAT2") (pin "2") (pinfunction "2_2") (pintype "passive"))
      (node (ref "C2") (pin "2") (pinfunction "2_2") (pintype "passive"))
      (node (ref "C2_BAT") (pin "2") (pinfunction "2_2") (pintype "passive"))
      (node (ref "C3") (pin "-") (pinfunction "-_-") (pintype "passive"))
      (node (ref "C4_USB") (pin "2") (pinfunction "2_2") (pintype "passive"))
      (node (ref "C5") (pin "2") (pinfunction "2_2") (pintype "passive"))
      (node (ref "C5_USB") (pin "2") (pinfunction "2_2") (pintype "passive"))
      (node (ref "C6") (pin "2") (pinfunction "2_2") (pintype "passive"))
      (node (ref "C8") (pin "2") (pinfunction "2_2") (pintype "passive"))
      (node (ref "C9") (pin "2") (pinfunction "2_2") (pintype "passive"))
      (node (ref "CHANGE_BUTTON") (pin "1") (pinfunction "1_1") (pintype "passive"))
      (node (ref "CHANGE_BUTTON") (pin "2") (pinfunction "2_2") (pintype "passive"))
      (node (ref "C_DELAY") (pin "2") (pinfunction "2_2") (pintype "passive"))
      (node (ref "D1") (pin "2") (pinfunction "GND_2") (pintype "bidirectional"))
      (node (ref "D10") (pin "1") (pinfunction "1_1") (pintype "passive"))
      (node (ref "D11") (pin "1") (pinfunction "1_1") (pintype "passive"))
      (node (ref "D12") (pin "1") (pinfunction "1_1") (pintype "passive"))
      (node (ref "D4") (pin "1") (pinfunction "K_1") (pintype "bidirectional"))
      (node (ref "D6") (pin "1") (pinfunction "1_1") (pintype "passive"))
      (node (ref "D8") (pin "1") (pinfunction "1_1") (pintype "passive"))
      (node (ref "D9") (pin "1") (pinfunction "1_1") (pintype "passive"))
      (node (ref "EPD_C1") (pin "1") (pinfunction "1_1") (pintype "passive"))
      (node (ref "EPD_C10") (pin "1") (pinfunction "1_1") (pintype "passive"))
      (node (ref "EPD_C11") (pin "1") (pinfunction "1_1") (pintype "passive"))
      (node (ref "EPD_C12") (pin "1") (pinfunction "1_1") (pintype "passive"))
      (node (ref "EPD_C2") (pin "1") (pinfunction "1_1") (pintype "passive"))
      (node (ref "EPD_C5") (pin "1") (pinfunction "1_1") (pintype "passive"))
      (node (ref "EPD_C6") (pin "1") (pinfunction "1_1") (pintype "passive"))
      (node (ref "EPD_C7") (pin "1") (pinfunction "1_1") (pintype "passive"))
      (node (ref "EPD_C8") (pin "1") (pinfunction "1_1") (pintype "passive"))
      (node (ref "EPD_C9") (pin "1") (pinfunction "1_1") (pintype "passive"))
      (node (ref "IC1") (pin "3") (pinfunction "GND_3") (pintype "bidirectional"))
      (node (ref "IC4") (pin "2") (pinfunction "VSS_2") (pintype "bidirectional"))
      (node (ref "J1") (pin "17") (pinfunction "17_17") (pintype "bidirectional"))
      (node (ref "J1") (pin "8") (pinfunction "8_8") (pintype "bidirectional"))
      (node (ref "J1") (pin "MP1") (pinfunction "MP1_MP1") (pintype "bidirectional"))
      (node (ref "J1") (pin "MP2") (pinfunction "MP2_MP2") (pintype "bidirectional"))
      (node (ref "J2") (pin "A1") (pinfunction "A1_A1") (pintype "bidirectional"))
      (node (ref "J2") (pin "A12") (pinfunction "A12_A12") (pintype "bidirectional"))
      (node (ref "J2") (pin "B1") (pinfunction "B1_B1") (pintype "bidirectional"))
      (node (ref "J2") (pin "B12") (pinfunction "B12_B12") (pintype "bidirectional"))
      (node (ref "J2") (pin "MP1") (pinfunction "MP1_MP1") (pintype "bidirectional"))
      (node (ref "J2") (pin "MP2") (pinfunction "MP2_MP2") (pintype "bidirectional"))
      (node (ref "J2") (pin "MP3") (pinfunction "MP3_MP3") (pintype "bidirectional"))
      (node (ref "J2") (pin "MP4") (pinfunction "MP4_MP4") (pintype "bidirectional"))
      (node (ref "J3") (pin "4") (pinfunction "4_4") (pintype "passive"))
      (node (ref "J4") (pin "G1") (pinfunction "GND_1_G1") (pintype "bidirectional"))
      (node (ref "J4") (pin "G2") (pinfunction "GND_2_G2") (pintype "bidirectional"))
      (node (ref "J4") (pin "G3") (pinfunction "GND_3_G3") (pintype "bidirectional"))
      (node (ref "J4") (pin "G4") (pinfunction "GND_4_G4") (pintype "bidirectional"))
      (node (ref "J4") (pin "P6") (pinfunction "VSS_P6") (pintype "bidirectional"))
      (node (ref "MCP73831") (pin "2") (pinfunction "VSS_2") (pintype "power_in"))
      (node (ref "R1_PWRUSB") (pin "1") (pinfunction "1_1") (pintype "passive"))
      (node (ref "R2") (pin "1") (pinfunction "1_1") (pintype "passive"))
      (node (ref "R2-USB") (pin "2") (pinfunction "2_2") (pintype "passive"))
      (node (ref "R2-USB1") (pin "1") (pinfunction "1_1") (pintype "passive"))
      (node (ref "R2_BAT") (pin "1") (pinfunction "1_1") (pintype "passive"))
      (node (ref "R4") (pin "1") (pinfunction "1_1") (pintype "passive"))
      (node (ref "RESET_BUTTON") (pin "1") (pinfunction "1_1") (pintype "passive"))
      (node (ref "RESET_BUTTON") (pin "2") (pinfunction "2_2") (pintype "passive"))
      (node (ref "SENSOR2") (pin "1") (pinfunction "GND_1") (pintype "power_in"))
      (node (ref "SENSOR2") (pin "5") (pinfunction "SDO_5") (pintype "bidirectional"))
      (node (ref "SENSOR2") (pin "7") (pinfunction "GND_7") (pintype "power_in"))
      (node (ref "SJ1") (pin "1") (pinfunction "1_1") (pintype "passive"))
      (node (ref "TP4") (pin "TP") (pinfunction "TP_TP") (pintype "input"))
      (node (ref "TP5") (pin "TP") (pinfunction "TP_TP") (pintype "input"))
      (node (ref "U1") (pin "4") (pinfunction "GND_4") (pintype "power_in"))
      (node (ref "U1") (pin "9") (pinfunction "EXP_9") (pintype "passive"))
      (node (ref "U2") (pin "1") (pinfunction "GND_1") (pintype "power_in"))
      (node (ref "U2") (pin "28") (pinfunction "GND_28") (pintype "power_in"))
      (node (ref "U2") (pin "29_1") (pinfunction "GND_29_1") (pintype "power_in"))
      (node (ref "U2") (pin "29_2") (pinfunction "GND_29_2") (pintype "power_in"))
      (node (ref "U2") (pin "29_3") (pinfunction "GND_29_3") (pintype "power_in"))
      (node (ref "U2") (pin "29_4") (pinfunction "GND_29_4") (pintype "power_in"))
      (node (ref "U2") (pin "29_5") (pinfunction "GND_29_5") (pintype "power_in"))
      (node (ref "U2") (pin "29_6") (pinfunction "GND_29_6") (pintype "power_in"))
      (node (ref "U2") (pin "29_7") (pinfunction "GND_29_7") (pintype "power_in"))
      (node (ref "U2") (pin "29_8") (pinfunction "GND_29_8") (pintype "power_in"))
      (node (ref "U2") (pin "29_9") (pinfunction "GND_29_9") (pintype "power_in"))
      (node (ref "U3") (pin "13") (pinfunction "GND_13") (pintype "power_in"))
      (node (ref "U4") (pin "1") (pinfunction "CTG_1") (pintype "power_in"))
      (node (ref "U4") (pin "4") (pinfunction "GND_4") (pintype "power_in"))
      (node (ref "U4") (pin "6") (pinfunction "QSTRT_6") (pintype "input"))
      (node (ref "U4") (pin "9") (pinfunction "EP_9") (pintype "power_in"))
    )
    (net (code "15") (name "GPIO8") (class "Default")
      (node (ref "R1") (pin "1") (pinfunction "1_1") (pintype "passive"))
      (node (ref "U2") (pin "10") (pinfunction "IO8_10") (pintype "bidirectional"))
    )
    (net (code "16") (name "I2C_PW") (class "Default")
      (node (ref "C1") (pin "1") (pinfunction "1_1") (pintype "passive"))
      (node (ref "C2") (pin "1") (pinfunction "1_1") (pintype "passive"))
      (node (ref "R1_PINH") (pin "2") (pinfunction "2_2") (pintype "passive"))
      (node (ref "R2_PINH") (pin "2") (pinfunction "2_2") (pintype "passive"))
      (node (ref "SENSOR2") (pin "2") (pinfunction "CSB_2") (pintype "input"))
      (node (ref "SENSOR2") (pin "6") (pinfunction "VDDIO_6") (pintype "power_in"))
      (node (ref "SENSOR2") (pin "8") (pinfunction "VDD_8") (pintype "power_in"))
    )
    (net (code "17") (name "INT_RTC") (class "Default")
      (node (ref "R1_PINH1") (pin "1") (pinfunction "1_1") (pintype "passive"))
      (node (ref "TP15") (pin "TP") (pinfunction "TP_TP") (pintype "input"))
      (node (ref "U2") (pin "8") (pinfunction "IO0_8") (pintype "bidirectional"))
      (node (ref "U3") (pin "3") (pinfunction "SQW/~{INT}_3") (pintype "output"))
    )
    (net (code "18") (name "IO{slash}BOOT") (class "Default")
      (node (ref "BOOT_BUTTON") (pin "3") (pinfunction "3_3") (pintype "passive"))
      (node (ref "BOOT_BUTTON") (pin "4") (pinfunction "4_4") (pintype "passive"))
      (node (ref "C6") (pin "1") (pinfunction "1_1") (pintype "passive"))
      (node (ref "R_BOOT") (pin "1") (pinfunction "1_1") (pintype "passive"))
      (node (ref "U2") (pin "15") (pinfunction "IO9_15") (pintype "bidirectional"))
    )
    (net (code "19") (name "IO{slash}CHANGE") (class "Default")
      (node (ref "C10") (pin "1") (pinfunction "1_1") (pintype "passive"))
      (node (ref "CHANGE_BUTTON") (pin "3") (pinfunction "3_3") (pintype "passive"))
      (node (ref "CHANGE_BUTTON") (pin "4") (pinfunction "4_4") (pintype "passive"))
      (node (ref "R_CHANGE") (pin "1") (pinfunction "1_1") (pintype "passive"))
      (node (ref "U2") (pin "23") (pinfunction "IO15_23") (pintype "bidirectional"))
    )
    (net (code "20") (name "MISO") (class "Default")
      (node (ref "J4") (pin "P7") (pinfunction "DAT0_P7") (pintype "bidirectional"))
      (node (ref "TP6") (pin "TP") (pinfunction "TP_TP") (pintype "input"))
      (node (ref "U1") (pin "2") (pinfunction "DO(IO1)_2") (pintype "bidirectional"))
      (node (ref "U2") (pin "27") (pinfunction "IO2_27") (pintype "bidirectional"))
    )
    (net (code "21") (name "MOSI") (class "Default")
      (node (ref "J1") (pin "14") (pinfunction "14_14") (pintype "bidirectional"))
      (node (ref "J4") (pin "P3") (pinfunction "CMD_P3") (pintype "bidirectional"))
      (node (ref "TP7") (pin "TP") (pinfunction "TP_TP") (pintype "input"))
      (node (ref "U1") (pin "5") (pinfunction "DI(IO0)_5") (pintype "bidirectional"))
      (node (ref "U2") (pin "7") (pinfunction "IO7_7") (pintype "bidirectional"))
    )
    (net (code "22") (name "N$7") (class "Default")
      (node (ref "Q3") (pin "1") (pinfunction "G_1") (pintype "bidirectional"))
      (node (ref "R4") (pin "2") (pinfunction "2_2") (pintype "passive"))
    )
    (net (code "23") (name "N$19") (class "Default")
      (node (ref "EPD_C5") (pin "2") (pinfunction "2_2") (pintype "passive"))
      (node (ref "J1") (pin "15") (pinfunction "15_15") (pintype "bidirectional"))
      (node (ref "J1") (pin "16") (pinfunction "16_16") (pintype "bidirectional"))
    )
    (net (code "24") (name "Net-(CHG_LED-PadC)") (class "Default")
      (node (ref "CHG_LED") (pin "C") (pinfunction "C_C") (pintype "passive"))
      (node (ref "R1_BAT") (pin "1") (pinfunction "1_1") (pintype "passive"))
    )
    (net (code "25") (name "Net-(D2-CATHODE)") (class "Default")
      (node (ref "C1_BAT1") (pin "1") (pinfunction "1_1") (pintype "passive"))
      (node (ref "D2") (pin "1") (pinfunction "CATHODE_1") (pintype "bidirectional"))
      (node (ref "IC4") (pin "1") (pinfunction "VIN_1") (pintype "bidirectional"))
      (node (ref "IC4") (pin "3") (pinfunction "CE_3") (pintype "bidirectional"))
      (node (ref "Q1") (pin "2") (pinfunction "S_2") (pintype "bidirectional"))
    )
    (net (code "26") (name "Net-(D3-K)") (class "Default")
      (node (ref "C4") (pin "1") (pinfunction "1_1") (pintype "passive"))
      (node (ref "D3") (pin "1") (pinfunction "K_1") (pintype "bidirectional"))
      (node (ref "D4") (pin "2") (pinfunction "A_2") (pintype "bidirectional"))
    )
    (net (code "27") (name "Net-(D7-CATHODE)") (class "Default")
      (node (ref "D7") (pin "1") (pinfunction "CATHODE_1") (pintype "bidirectional"))
      (node (ref "R_CAPACITOR") (pin "1") (pinfunction "1_1") (pintype "passive"))
    )
    (net (code "28") (name "Net-(D8-Pad2)") (class "Default")
      (node (ref "D8") (pin "2") (pinfunction "2_2") (pintype "passive"))
      (node (ref "R10") (pin "1") (pinfunction "1_1") (pintype "passive"))
    )
    (net (code "29") (name "Net-(D12-Pad2)") (class "Default")
      (node (ref "D12") (pin "2") (pinfunction "2_2") (pintype "passive"))
      (node (ref "R8") (pin "1") (pinfunction "1_1") (pintype "passive"))
    )
    (net (code "30") (name "Net-(EPD_C1-Pad2)") (class "Default")
      (node (ref "EPD_C1") (pin "2") (pinfunction "2_2") (pintype "passive"))
      (node (ref "J1") (pin "4") (pinfunction "4_4") (pintype "bidirectional"))
    )
    (net (code "31") (name "Net-(EPD_C2-Pad2)") (class "Default")
      (node (ref "EPD_C2") (pin "2") (pinfunction "2_2") (pintype "passive"))
      (node (ref "J1") (pin "5") (pinfunction "5_5") (pintype "bidirectional"))
    )
    (net (code "32") (name "Net-(EPD_C6-Pad2)") (class "Default")
      (node (ref "EPD_C6") (pin "2") (pinfunction "2_2") (pintype "passive"))
      (node (ref "J1") (pin "18") (pinfunction "18_18") (pintype "bidirectional"))
    )
    (net (code "33") (name "Net-(EPD_C7-Pad2)") (class "Default")
      (node (ref "EPD_C7") (pin "2") (pinfunction "2_2") (pintype "passive"))
      (node (ref "J1") (pin "19") (pinfunction "19_19") (pintype "bidirectional"))
    )
    (net (code "34") (name "Net-(EPD_C8-Pad2)") (class "Default")
      (node (ref "EPD_C8") (pin "2") (pinfunction "2_2") (pintype "passive"))
      (node (ref "J1") (pin "20") (pinfunction "20_20") (pintype "bidirectional"))
    )
    (net (code "35") (name "Net-(EPD_C9-Pad2)") (class "Default")
      (node (ref "EPD_C9") (pin "2") (pinfunction "2_2") (pintype "passive"))
      (node (ref "J1") (pin "21") (pinfunction "21_21") (pintype "bidirectional"))
    )
    (net (code "36") (name "Net-(EPD_C10-Pad2)") (class "Default")
      (node (ref "EPD_C10") (pin "2") (pinfunction "2_2") (pintype "passive"))
      (node (ref "J1") (pin "22") (pinfunction "22_22") (pintype "bidirectional"))
    )
    (net (code "37") (name "Net-(EPD_C11-Pad2)") (class "Default")
      (node (ref "EPD_C11") (pin "2") (pinfunction "2_2") (pintype "passive"))
      (node (ref "J1") (pin "23") (pinfunction "23_23") (pintype "bidirectional"))
    )
    (net (code "38") (name "Net-(EPD_C12-Pad2)") (class "Default")
      (node (ref "EPD_C12") (pin "2") (pinfunction "2_2") (pintype "passive"))
      (node (ref "J1") (pin "24") (pinfunction "24_24") (pintype "bidirectional"))
    )
    (net (code "39") (name "Net-(IC1-CT)") (class "Default")
      (node (ref "C_DELAY") (pin "1") (pinfunction "1_1") (pintype "passive"))
      (node (ref "IC1") (pin "5") (pinfunction "CT_5") (pintype "bidirectional"))
    )
    (net (code "40") (name "Net-(J2-PadA5)") (class "Default")
      (node (ref "J2") (pin "A5") (pinfunction "A5_A5") (pintype "bidirectional"))
      (node (ref "R2-USB1") (pin "2") (pinfunction "2_2") (pintype "passive"))
    )
    (net (code "41") (name "Net-(J2-PadB5)") (class "Default")
      (node (ref "J2") (pin "B5") (pinfunction "B5_B5") (pintype "bidirectional"))
      (node (ref "R2-USB") (pin "1") (pinfunction "1_1") (pintype "passive"))
    )
    (net (code "42") (name "Net-(MCP73831-PROG)") (class "Default")
      (node (ref "MCP73831") (pin "5") (pinfunction "PROG_5") (pintype "input"))
      (node (ref "R2_BAT") (pin "2") (pinfunction "2_2") (pintype "passive"))
    )
    (net (code "43") (name "Net-(MCP73831-STAT)") (class "Default")
      (node (ref "MCP73831") (pin "1") (pinfunction "STAT_1") (pintype "output"))
      (node (ref "R1_BAT") (pin "2") (pinfunction "2_2") (pintype "passive"))
    )
    (net (code "44") (name "PREVGH") (class "Default")
      (node (ref "D5") (pin "1") (pinfunction "K_1") (pintype "bidirectional"))
    )
    (net (code "45") (name "PREVGL") (class "Default")
      (node (ref "D3") (pin "2") (pinfunction "A_2") (pintype "bidirectional"))
    )
    (net (code "46") (name "RESE") (class "Default")
      (node (ref "J1") (pin "3") (pinfunction "3_3") (pintype "bidirectional"))
      (node (ref "Q3") (pin "2") (pinfunction "S_2") (pintype "bidirectional"))
      (node (ref "R3") (pin "2") (pinfunction "2_2") (pintype "passive"))
    )
    (net (code "47") (name "RESE'") (class "Default")
      (node (ref "R2") (pin "2") (pinfunction "2_2") (pintype "passive"))
      (node (ref "R3") (pin "1") (pinfunction "1_1") (pintype "passive"))
      (node (ref "SJ1") (pin "2") (pinfunction "2_2") (pintype "passive"))
    )
    (net (code "48") (name "RESET") (class "Default")
      (node (ref "C5") (pin "1") (pinfunction "1_1") (pintype "passive"))
      (node (ref "IC1") (pin "1") (pinfunction "VOUT_1") (pintype "bidirectional"))
      (node (ref "RESET_BUTTON") (pin "3") (pinfunction "3_3") (pintype "passive"))
      (node (ref "RESET_BUTTON") (pin "4") (pinfunction "4_4") (pintype "passive"))
      (node (ref "R_RESET") (pin "2") (pinfunction "2_2") (pintype "passive"))
      (node (ref "U2") (pin "3") (pinfunction "EN_3") (pintype "input"))
    )
    (net (code "49") (name "RTC_RST") (class "Default")
      (node (ref "U2") (pin "16") (pinfunction "IO18_16") (pintype "bidirectional"))
      (node (ref "U3") (pin "4") (pinfunction "~{RST}_4") (pintype "input"))
    )
    (net (code "50") (name "RX") (class "Default")
      (node (ref "TP2") (pin "TP") (pinfunction "TP_TP") (pintype "input"))
      (node (ref "U2") (pin "24") (pinfunction "RXD0/GPIO17_24") (pintype "bidirectional"))
    )
    (net (code "51") (name "SCK") (class "Default")
      (node (ref "J1") (pin "13") (pinfunction "13_13") (pintype "bidirectional"))
      (node (ref "J4") (pin "P5") (pinfunction "CLK_P5") (pintype "bidirectional"))
      (node (ref "TP8") (pin "TP") (pinfunction "TP_TP") (pintype "input"))
      (node (ref "U1") (pin "6") (pinfunction "CLK_6") (pintype "input"))
      (node (ref "U2") (pin "6") (pinfunction "IO6_6") (pintype "bidirectional"))
    )
    (net (code "52") (name "SCL") (class "Default")
      (node (ref "J3") (pin "1") (pinfunction "1_1") (pintype "power_in"))
      (node (ref "R2_PINH") (pin "1") (pinfunction "1_1") (pintype "passive"))
      (node (ref "SENSOR2") (pin "4") (pinfunction "SCK_4") (pintype "input"))
      (node (ref "U2") (pin "20") (pinfunction "IO22_20") (pintype "bidirectional"))
      (node (ref "U3") (pin "16") (pinfunction "SCL_16") (pintype "input"))
      (node (ref "U4") (pin "7") (pinfunction "SCL_7") (pintype "input"))
    )
    (net (code "53") (name "SDA") (class "Default")
      (node (ref "J3") (pin "2") (pinfunction "2_2") (pintype "power_in"))
      (node (ref "R1_PINH") (pin "1") (pinfunction "1_1") (pintype "passive"))
      (node (ref "SENSOR2") (pin "3") (pinfunction "SDI_3") (pintype "bidirectional"))
      (node (ref "U2") (pin "19") (pinfunction "IO21_19") (pintype "bidirectional"))
      (node (ref "U3") (pin "15") (pinfunction "SDA_15") (pintype "bidirectional"))
      (node (ref "U4") (pin "8") (pinfunction "SDA_8") (pintype "bidirectional"))
    )
    (net (code "54") (name "SRC") (class "Default")
      (node (ref "C4") (pin "2") (pinfunction "2_2") (pintype "passive"))
      (node (ref "D5") (pin "2") (pinfunction "A_2") (pintype "bidirectional"))
      (node (ref "L1") (pin "1") (pinfunction "1_1") (pintype "passive"))
      (node (ref "Q3") (pin "3") (pinfunction "D_3") (pintype "bidirectional"))
    )
    (net (code "55") (name "SS_SD") (class "Default")
      (node (ref "J4") (pin "P2") (pinfunction "CD/DAT3_P2") (pintype "bidirectional"))
      (node (ref "U2") (pin "4") (pinfunction "IO4_4") (pintype "bidirectional"))
    )
    (net (code "56") (name "TX") (class "Default")
      (node (ref "TP1") (pin "TP") (pinfunction "TP_TP") (pintype "input"))
      (node (ref "U2") (pin "25") (pinfunction "TXD0/GPIO16_25") (pintype "bidirectional"))
    )
    (net (code "57") (name "USB_D+") (class "Default")
      (node (ref "D1") (pin "1") (pinfunction "I/O1_1_1") (pintype "bidirectional"))
      (node (ref "U2") (pin "14") (pinfunction "IO13_14") (pintype "bidirectional"))
    )
    (net (code "58") (name "USB_D-") (class "Default")
      (node (ref "D1") (pin "3") (pinfunction "I/O2_1_3") (pintype "bidirectional"))
      (node (ref "U2") (pin "13") (pinfunction "IO12_13") (pintype "bidirectional"))
    )
    (net (code "59") (name "VBAT") (class "Default")
      (node (ref "C2_BAT") (pin "1") (pinfunction "1_1") (pintype "passive"))
      (node (ref "MCP73831") (pin "3") (pinfunction "VBAT_3") (pintype "power_in"))
      (node (ref "Q1") (pin "3") (pinfunction "D_3") (pintype "bidirectional"))
      (node (ref "TP3") (pin "TP") (pinfunction "TP_TP") (pintype "input"))
      (node (ref "U4") (pin "2") (pinfunction "CELL_2") (pintype "power_in"))
      (node (ref "U4") (pin "3") (pinfunction "VDD_3") (pintype "power_in"))
    )
    (net (code "60") (name "VBUS") (class "Default")
      (node (ref "C1_BAT") (pin "1") (pinfunction "1_1") (pintype "passive"))
      (node (ref "C4_USB") (pin "1") (pinfunction "1_1") (pintype "passive"))
      (node (ref "C5_USB") (pin "1") (pinfunction "1_1") (pintype "passive"))
      (node (ref "CHG_LED") (pin "A") (pinfunction "A_A") (pintype "passive"))
      (node (ref "D1") (pin "5") (pinfunction "VBUS_5") (pintype "bidirectional"))
      (node (ref "D2") (pin "2") (pinfunction "ANODE_2") (pintype "bidirectional"))
      (node (ref "MCP73831") (pin "4") (pinfunction "VIN_4") (pintype "power_in"))
      (node (ref "PFMF.050.1") (pin "2") (pinfunction "2_2") (pintype "passive"))
      (node (ref "Q1") (pin "1") (pinfunction "G_1") (pintype "bidirectional"))
      (node (ref "R1_PWRUSB") (pin "2") (pinfunction "2_2") (pintype "passive"))
      (node (ref "TP14") (pin "TP") (pinfunction "TP_TP") (pintype "input"))
    )
    (net (code "61") (name "VRTC") (class "Default")
      (node (ref "C10_SUPERCAP") (pin "1") (pinfunction "1_1") (pintype "passive"))
      (node (ref "C8") (pin "1") (pinfunction "1_1") (pintype "passive"))
      (node (ref "R_CAPACITOR") (pin "2") (pinfunction "2_2") (pintype "passive"))
      (node (ref "U3") (pin "14") (pinfunction "VBAT_14") (pintype "power_in"))
    )
    (net (code "62") (name "VUSB") (class "Default")
      (node (ref "J2") (pin "A4") (pinfunction "A4_A4") (pintype "bidirectional"))
      (node (ref "J2") (pin "A9") (pinfunction "A9_A9") (pintype "bidirectional"))
      (node (ref "J2") (pin "B4") (pinfunction "B4_B4") (pintype "bidirectional"))
      (node (ref "J2") (pin "B9") (pinfunction "B9_B9") (pintype "bidirectional"))
      (node (ref "PFMF.050.1") (pin "1") (pinfunction "1_1") (pintype "passive"))
    )
    (net (code "63") (name "unconnected-(C7-Pad2)") (class "Default")
      (node (ref "C7") (pin "2") (pinfunction "2_2") (pintype "passive"))
    )
    (net (code "64") (name "unconnected-(D6-Pad2)") (class "Default")
      (node (ref "D6") (pin "2") (pinfunction "2_2") (pintype "passive"))
    )
    (net (code "65") (name "unconnected-(D9-Pad2)") (class "Default")
      (node (ref "D9") (pin "2") (pinfunction "2_2") (pintype "passive"))
    )
    (net (code "66") (name "unconnected-(D10-Pad2)") (class "Default")
      (node (ref "D10") (pin "2") (pinfunction "2_2") (pintype "passive"))
    )
    (net (code "67") (name "unconnected-(D11-Pad2)") (class "Default")
      (node (ref "D11") (pin "2") (pinfunction "2_2") (pintype "passive"))
    )
    (net (code "68") (name "unconnected-(IC1-NC-Pad4)") (class "Default")
      (node (ref "IC1") (pin "4") (pinfunction "NC_4") (pintype "no_connect"))
    )
    (net (code "69") (name "unconnected-(IC4-NC-Pad4)") (class "Default")
      (node (ref "IC4") (pin "4") (pinfunction "NC_4") (pintype "no_connect"))
    )
    (net (code "70") (name "unconnected-(J1-Pad1)") (class "Default")
      (node (ref "J1") (pin "1") (pinfunction "1_1") (pintype "bidirectional"))
    )
    (net (code "71") (name "unconnected-(J1-Pad6)") (class "Default")
      (node (ref "J1") (pin "6") (pinfunction "6_6") (pintype "bidirectional"))
    )
    (net (code "72") (name "unconnected-(J1-Pad7)") (class "Default")
      (node (ref "J1") (pin "7") (pinfunction "7_7") (pintype "bidirectional"))
    )
    (net (code "73") (name "unconnected-(J2-PadA8)") (class "Default")
      (node (ref "J2") (pin "A8") (pinfunction "A8_A8") (pintype "bidirectional"))
    )
    (net (code "74") (name "unconnected-(J2-PadB8)") (class "Default")
      (node (ref "J2") (pin "B8") (pinfunction "B8_B8") (pintype "bidirectional"))
    )
    (net (code "75") (name "unconnected-(J4-DAT1-PadP8)") (class "Default")
      (node (ref "J4") (pin "P8") (pinfunction "DAT1_P8") (pintype "bidirectional"))
    )
    (net (code "76") (name "unconnected-(J4-DAT2-PadP1)") (class "Default")
      (node (ref "J4") (pin "P1") (pinfunction "DAT2_P1") (pintype "bidirectional"))
    )
    (net (code "77") (name "unconnected-(J4-DETECTION_1-PadS1)") (class "Default")
      (node (ref "J4") (pin "S1") (pinfunction "DETECTION_1_S1") (pintype "bidirectional"))
    )
    (net (code "78") (name "unconnected-(J4-DETECTION_2-PadS2)") (class "Default")
      (node (ref "J4") (pin "S2") (pinfunction "DETECTION_2_S2") (pintype "bidirectional"))
    )
    (net (code "79") (name "unconnected-(R5-Pad1)") (class "Default")
      (node (ref "R5") (pin "1") (pinfunction "1_1") (pintype "passive"))
    )
    (net (code "80") (name "unconnected-(R6-Pad1)") (class "Default")
      (node (ref "R6") (pin "1") (pinfunction "1_1") (pintype "passive"))
    )
    (net (code "81") (name "unconnected-(R7-Pad1)") (class "Default")
      (node (ref "R7") (pin "1") (pinfunction "1_1") (pintype "passive"))
    )
    (net (code "82") (name "unconnected-(R9-Pad1)") (class "Default")
      (node (ref "R9") (pin "1") (pinfunction "1_1") (pintype "passive"))
    )
    (net (code "83") (name "unconnected-(U2-NC-Pad22)") (class "Default")
      (node (ref "U2") (pin "22") (pinfunction "NC_22") (pintype "no_connect"))
    )
    (net (code "84") (name "unconnected-(U4-~{ALERT}-Pad5)") (class "Default")
      (node (ref "U4") (pin "5") (pinfunction "~{ALERT}_5") (pintype "output"))
    )
  )
)
